# LED.net
KiCad netlist of a schematic drawn in Altium Designer
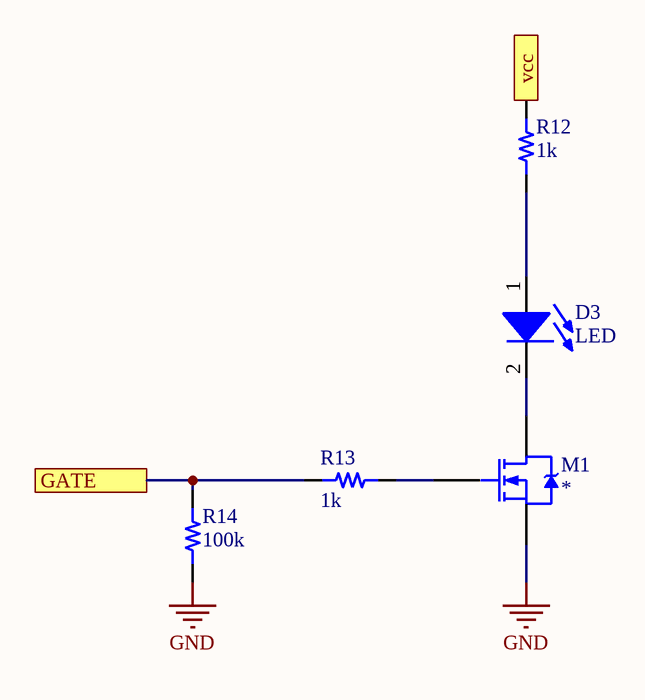
[diagram p0: LED.SchDoc]

(export (version "E")
  (design (tool "Eeschema 10.0.6"))
  (components
    (comp (ref "D3")
      (value "LED")
      (footprint "0805_LED")
      (description "Generic 0805 LED")
      (libsource (lib "altlib") (part "LED"))
    )
    (comp (ref "M1")
      (value "*")
      (footprint "SOT23-3")
      (description "MOSFET N-CHANNEL 30V 5A SOT23")
      (libsource (lib "altlib") (part "DMG2302UK-7"))
    )
    (comp (ref "R12")
      (value "~")
      (footprint "RES 0603/1608")
      (fields (field (name "RESISTANCE") "1k"))
      (libsource (lib "altlib") (part "Resistor"))
    )
    (comp (ref "R13")
      (value "~")
      (footprint "RES 0603/1608")
      (fields (field (name "RESISTANCE") "1k"))
      (libsource (lib "altlib") (part "Resistor"))
    )
    (comp (ref "R14")
      (value "~")
      (footprint "RES 0603/1608")
      (fields (field (name "RESISTANCE") "100k"))
      (libsource (lib "altlib") (part "Resistor"))
    )
  )
  (nets
    (net (code "1") (name "/GATE") (class "Default")
      (node (ref "R13") (pin "2") (pinfunction "2_2") (pintype "passive"))
      (node (ref "R14") (pin "2") (pinfunction "2_2") (pintype "passive"))
    )
    (net (code "2") (name "/vcc") (class "Default")
      (node (ref "R12") (pin "2") (pinfunction "2_2") (pintype "passive"))
    )
    (net (code "3") (name "GND") (class "Default")
      (node (ref "M1") (pin "2") (pinfunction "S_2") (pintype "passive"))
      (node (ref "R14") (pin "1") (pinfunction "1_1") (pintype "passive"))
    )
    (net (code "4") (name "Net-(D3-A)") (class "Default")
      (node (ref "D3") (pin "1") (pinfunction "A_1") (pintype "passive"))
      (node (ref "R12") (pin "1") (pinfunction "1_1") (pintype "passive"))
    )
    (net (code "5") (name "Net-(D3-K)") (class "Default")
      (node (ref "D3") (pin "2") (pinfunction "K_2") (pintype "passive"))
      (node (ref "M1") (pin "3") (pinfunction "D_3") (pintype "passive"))
    )
    (net (code "6") (name "Net-(M1-G)") (class "Default")
      (node (ref "M1") (pin "1") (pinfunction "G_1") (pintype "passive"))
      (node (ref "R13") (pin "1") (pinfunction "1_1") (pintype "passive"))
    )
  )
)
